# untitled.net
KiCad netlist of a schematic drawn in EAGLE
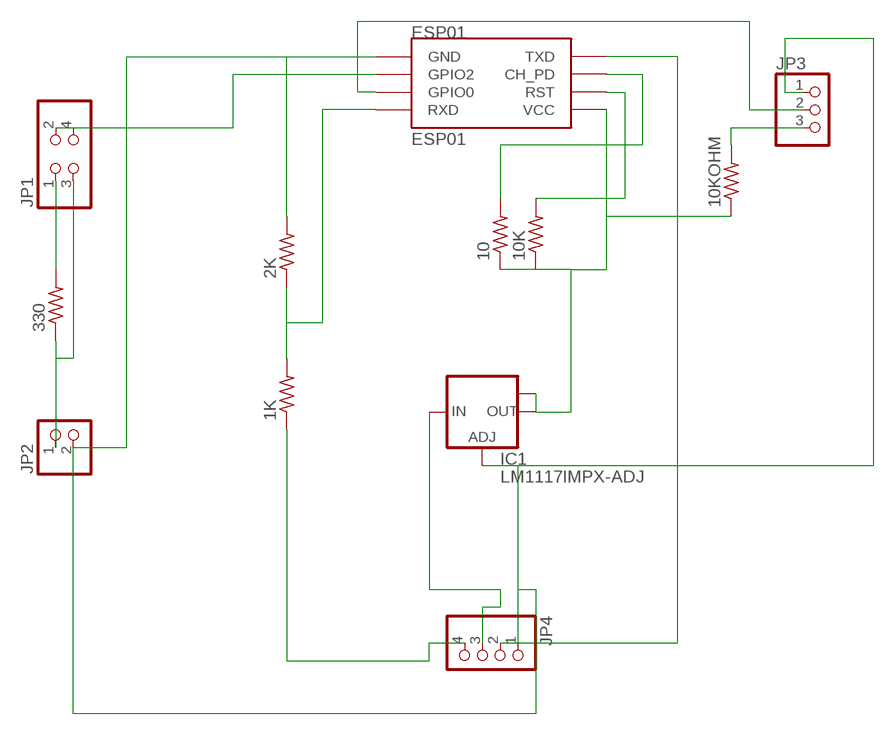
[diagram p0: schematic, sheet 1]

(export (version "E")
  (design (tool "Eeschema 10.0.6"))
  (components
    (comp (ref "1K")
      (value "R-US_0204/7")
      (footprint "eagle-import:0204_7")
      (libsource (lib "eagle-import") (part "R-US_0204/7"))
    )
    (comp (ref "2K")
      (value "R-US_0204/7")
      (footprint "eagle-import:0204_7")
      (libsource (lib "eagle-import") (part "R-US_0204/7"))
    )
    (comp (ref "10")
      (value "R-US_0204/7")
      (footprint "eagle-import:0204_7")
      (libsource (lib "eagle-import") (part "R-US_0204/7"))
    )
    (comp (ref "10K")
      (value "R-US_0204/7")
      (footprint "eagle-import:0204_7")
      (libsource (lib "eagle-import") (part "R-US_0204/7"))
    )
    (comp (ref "10KOHM")
      (value "R-US_0204/7")
      (footprint "eagle-import:0204_7")
      (libsource (lib "eagle-import") (part "R-US_0204/7"))
    )
    (comp (ref "330")
      (value "R-US_0204/7")
      (footprint "eagle-import:0204_7")
      (libsource (lib "eagle-import") (part "R-US_0204/7"))
    )
    (comp (ref "ESP01")
      (value "ESP01")
      (footprint "eagle-import:ESP01")
      (libsource (lib "eagle-import") (part "ESP01"))
    )
    (comp (ref "IC1")
      (value "LM1117IMPX-ADJ")
      (footprint "eagle-import:SOT223")
      (libsource (lib "eagle-import") (part "LM1117IMPX-ADJ"))
    )
    (comp (ref "JP1")
      (value "PINHD-2X2")
      (footprint "eagle-import:2X02")
      (libsource (lib "eagle-import") (part "PINHD-2X2"))
    )
    (comp (ref "JP2")
      (value "PINHD-1X2")
      (footprint "eagle-import:1X02")
      (libsource (lib "eagle-import") (part "PINHD-1X2"))
    )
    (comp (ref "JP3")
      (value "PINHD-1X3")
      (footprint "eagle-import:1X03")
      (libsource (lib "eagle-import") (part "PINHD-1X3"))
    )
    (comp (ref "JP4")
      (value "PINHD-1X4")
      (footprint "eagle-import:1X04")
      (libsource (lib "eagle-import") (part "PINHD-1X4"))
    )
  )
  (nets
    (net (code "1") (name "Net-(1K-Pad1)") (class "Default")
      (node (ref "1K") (pin "1") (pinfunction "1_1") (pintype "passive"))
      (node (ref "JP4") (pin "4") (pinfunction "4_4") (pintype "passive"))
    )
    (net (code "2") (name "Net-(10-Pad2)") (class "Default")
      (node (ref "10") (pin "2") (pinfunction "2_2") (pintype "passive"))
      (node (ref "ESP01") (pin "CH_PD") (pinfunction "CH_PD_CH_PD") (pintype "bidirectional"))
    )
    (net (code "3") (name "Net-(10K-Pad2)") (class "Default")
      (node (ref "10K") (pin "2") (pinfunction "2_2") (pintype "passive"))
      (node (ref "ESP01") (pin "RST") (pinfunction "RST_RST") (pintype "bidirectional"))
    )
    (net (code "4") (name "Net-(10KOHM-Pad2)") (class "Default")
      (node (ref "10KOHM") (pin "2") (pinfunction "2_2") (pintype "passive"))
      (node (ref "JP3") (pin "3") (pinfunction "3_3") (pintype "passive"))
    )
    (net (code "5") (name "Net-(330-Pad1)") (class "Default")
      (node (ref "330") (pin "1") (pinfunction "1_1") (pintype "passive"))
      (node (ref "JP1") (pin "3") (pinfunction "3_3") (pintype "passive"))
      (node (ref "JP2") (pin "1") (pinfunction "1_1") (pintype "passive"))
    )
    (net (code "6") (name "Net-(330-Pad2)") (class "Default")
      (node (ref "330") (pin "2") (pinfunction "2_2") (pintype "passive"))
      (node (ref "JP1") (pin "1") (pinfunction "1_1") (pintype "passive"))
    )
    (net (code "7") (name "Net-(ESP01-PadGPIO0)") (class "Default")
      (node (ref "ESP01") (pin "GPIO0") (pinfunction "GPIO0_GPIO0") (pintype "bidirectional"))
      (node (ref "JP3") (pin "2") (pinfunction "2_2") (pintype "passive"))
    )
    (net (code "8") (name "Net-(ESP01-PadGPIO2)") (class "Default")
      (node (ref "ESP01") (pin "GPIO2") (pinfunction "GPIO2_GPIO2") (pintype "bidirectional"))
      (node (ref "JP1") (pin "2") (pinfunction "2_2") (pintype "passive"))
      (node (ref "JP1") (pin "4") (pinfunction "4_4") (pintype "passive"))
    )
    (net (code "9") (name "Net-(ESP01-RXD)") (class "Default")
      (node (ref "1K") (pin "2") (pinfunction "2_2") (pintype "passive"))
      (node (ref "2K") (pin "1") (pinfunction "1_1") (pintype "passive"))
      (node (ref "ESP01") (pin "RX") (pinfunction "RXD_RX") (pintype "bidirectional"))
    )
    (net (code "10") (name "Net-(ESP01-TXD)") (class "Default")
      (node (ref "ESP01") (pin "TX") (pinfunction "TXD_TX") (pintype "bidirectional"))
      (node (ref "JP4") (pin "2") (pinfunction "2_2") (pintype "passive"))
    )
    (net (code "11") (name "Net-(IC1-ADJ)") (class "Default")
      (node (ref "2K") (pin "2") (pinfunction "2_2") (pintype "passive"))
      (node (ref "ESP01") (pin "GND") (pinfunction "GND_GND") (pintype "bidirectional"))
      (node (ref "IC1") (pin "1") (pinfunction "ADJ_1") (pintype "input"))
      (node (ref "JP2") (pin "2") (pinfunction "2_2") (pintype "passive"))
      (node (ref "JP3") (pin "1") (pinfunction "1_1") (pintype "passive"))
      (node (ref "JP4") (pin "1") (pinfunction "1_1") (pintype "passive"))
    )
    (net (code "12") (name "Net-(IC1-IN)") (class "Default")
      (node (ref "IC1") (pin "3") (pinfunction "IN_3") (pintype "input"))
      (node (ref "JP4") (pin "3") (pinfunction "3_3") (pintype "passive"))
    )
    (net (code "13") (name "Net-(IC1-OUT)") (class "Default")
      (node (ref "10") (pin "1") (pinfunction "1_1") (pintype "passive"))
      (node (ref "10K") (pin "1") (pinfunction "1_1") (pintype "passive"))
      (node (ref "10KOHM") (pin "1") (pinfunction "1_1") (pintype "passive"))
      (node (ref "ESP01") (pin "VCC") (pinfunction "VCC_VCC") (pintype "bidirectional"))
      (node (ref "IC1") (pin "2") (pinfunction "OUT_2") (pintype "passive"))
      (node (ref "IC1") (pin "TAB") (pinfunction "OUT1_TAB") (pintype "passive"))
    )
  )
)
